# PCB_SATA_SFP.net
KiCad netlist of a schematic drawn in Altium Designer
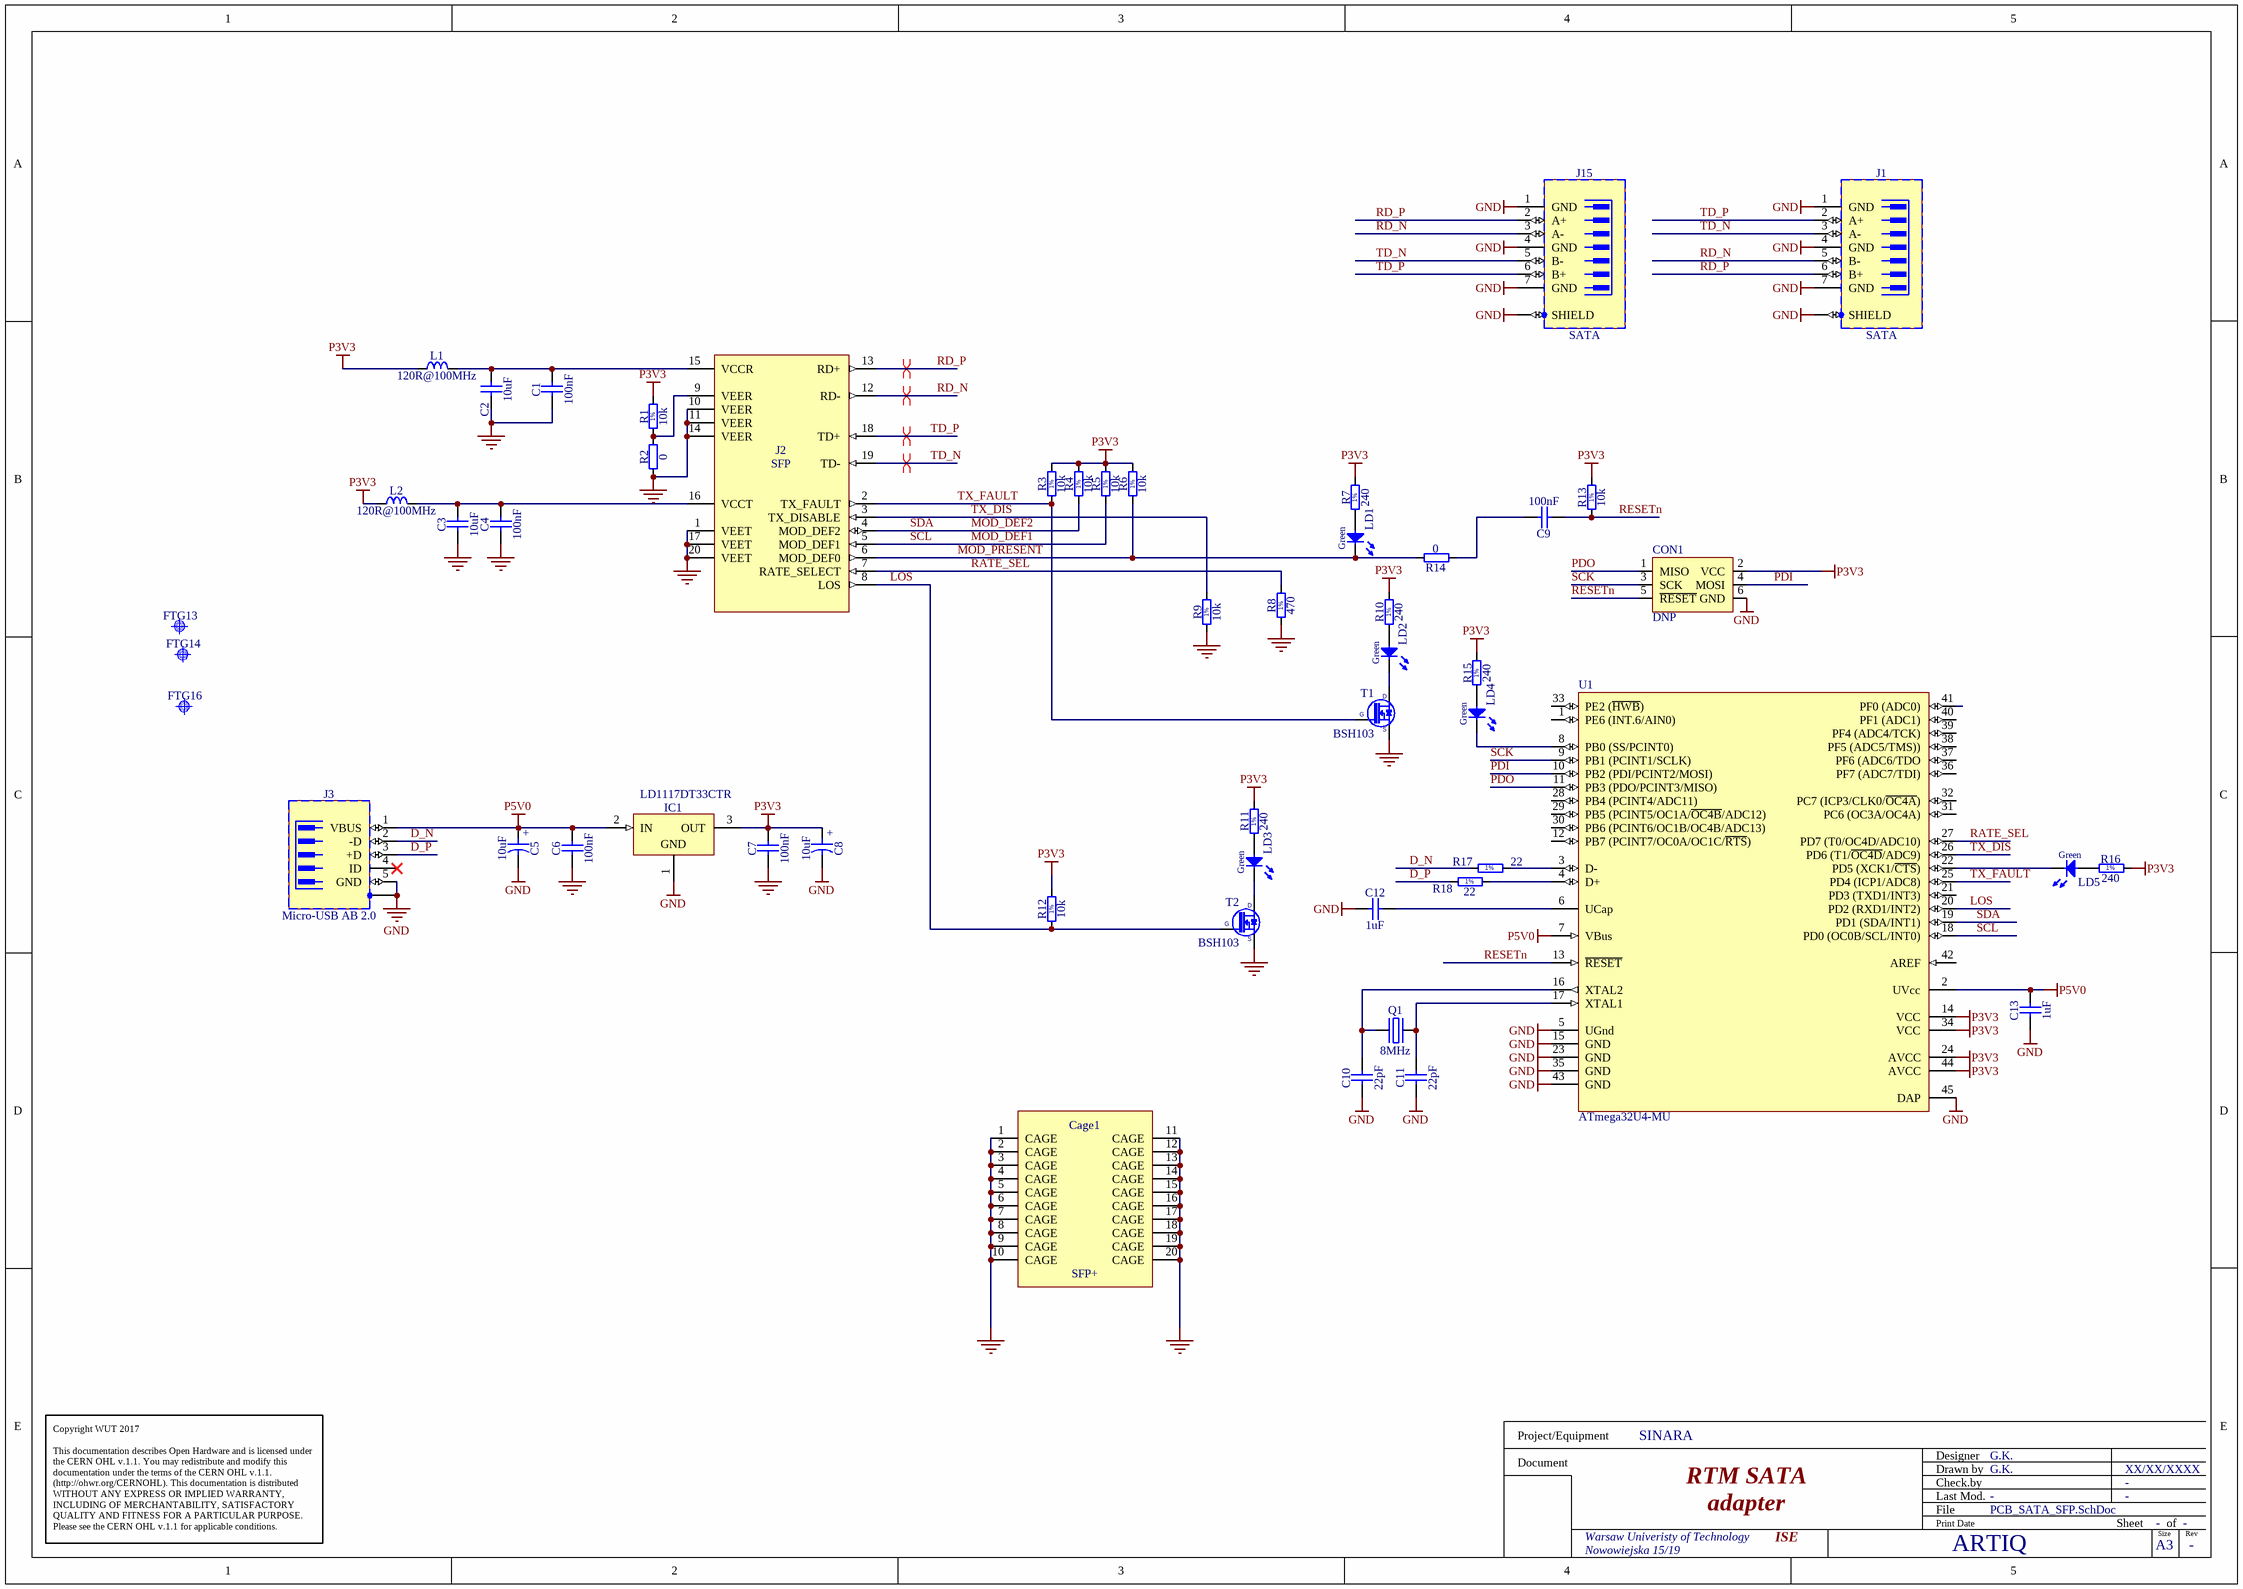
[diagram p0: PCB_SATA_SFP.SchDoc]

(export (version "E")
  (design (tool "Eeschema 10.0.6"))
  (components
    (comp (ref "C1")
      (value "100nF")
      (footprint "CAPC1608X87N")
      (description "Non-polarised capacitor")
      (fields
        (field (name "PART NUMBER") "CC0603_100NF_50V_10%_X5R")
        (field (name "VOLTAGE") "50V")
        (field (name "AUTHOR") "CERN DEM MR")
      )
      (libsource (lib "Capacitors") (part "Capacitor - non polarized"))
    )
    (comp (ref "C2")
      (value "10uF")
      (footprint "CAPC2012X95N")
      (description "Non-polarised capacitor")
      (fields
        (field (name "PART NUMBER") "CC0805_10UF_25V_10%_X5R")
        (field (name "VOLTAGE") "25V")
        (field (name "AUTHOR") "CERN DEM JLC")
      )
      (libsource (lib "Capacitors") (part "Capacitor - non polarized"))
    )
    (comp (ref "C3")
      (value "10uF")
      (footprint "CAPC2012X95N")
      (description "Non-polarised capacitor")
      (fields
        (field (name "PART NUMBER") "CC0805_10UF_25V_10%_X5R")
        (field (name "VOLTAGE") "25V")
        (field (name "AUTHOR") "CERN DEM JLC")
      )
      (libsource (lib "Capacitors") (part "Capacitor - non polarized"))
    )
    (comp (ref "C4")
      (value "100nF")
      (footprint "CAPC1608X87N")
      (description "Non-polarised capacitor")
      (fields
        (field (name "PART NUMBER") "CC0603_100NF_50V_10%_X5R")
        (field (name "VOLTAGE") "50V")
        (field (name "AUTHOR") "CERN DEM MR")
      )
      (libsource (lib "Capacitors") (part "Capacitor - non polarized"))
    )
    (comp (ref "C5")
      (value "10uF")
      (footprint "CAPMP6032X280N")
      (description "Polarised capacitor")
      (fields
        (field (name "PART NUMBER") "CTE6032-28_10UF_25V_10%_LESR0300")
        (field (name "VOLTAGE") "25V")
        (field (name "AUTHOR") "CERN DEM JLC")
      )
      (libsource (lib "Capacitors") (part "Capacitor - polarized"))
    )
    (comp (ref "C6")
      (value "100nF")
      (footprint "CAPC1608X87N")
      (description "Non-polarised capacitor")
      (fields
        (field (name "PART NUMBER") "CC0603_100NF_50V_10%_X5R")
        (field (name "VOLTAGE") "50V")
        (field (name "AUTHOR") "CERN DEM MR")
      )
      (libsource (lib "Capacitors") (part "Capacitor - non polarized"))
    )
    (comp (ref "C7")
      (value "100nF")
      (footprint "CAPC1608X87N")
      (description "Non-polarised capacitor")
      (fields
        (field (name "PART NUMBER") "CC0603_100NF_50V_10%_X5R")
        (field (name "VOLTAGE") "50V")
        (field (name "AUTHOR") "CERN DEM MR")
      )
      (libsource (lib "Capacitors") (part "Capacitor - non polarized"))
    )
    (comp (ref "C8")
      (value "10uF")
      (footprint "CAPMP6032X280N")
      (description "Polarised capacitor")
      (fields
        (field (name "PART NUMBER") "CTE6032-28_10UF_25V_10%_LESR0300")
        (field (name "VOLTAGE") "25V")
        (field (name "AUTHOR") "CERN DEM JLC")
      )
      (libsource (lib "Capacitors") (part "Capacitor - polarized"))
    )
    (comp (ref "C9")
      (value "100nF")
      (footprint "CAPC1608X87N")
      (description "Non-polarised capacitor")
      (fields
        (field (name "PART NUMBER") "CC0603_100NF_50V_10%_X5R")
        (field (name "VOLTAGE") "50V")
        (field (name "AUTHOR") "CERN DEM MR")
      )
      (libsource (lib "Capacitors") (part "Capacitor - non polarized"))
    )
    (comp (ref "C10")
      (value "22pF")
      (footprint "CAPC1608X87N")
      (description "Non-polarised capacitor")
      (fields
        (field (name "PART NUMBER") "CC0603_22PF_50V_5%_NP0")
        (field (name "VOLTAGE") "50V")
        (field (name "AUTHOR") "CERN DEM JLC")
      )
      (libsource (lib "Capacitors") (part "Capacitor - non polarized"))
    )
    (comp (ref "C11")
      (value "22pF")
      (footprint "CAPC1608X87N")
      (description "Non-polarised capacitor")
      (fields
        (field (name "PART NUMBER") "CC0603_22PF_50V_5%_NP0")
        (field (name "VOLTAGE") "50V")
        (field (name "AUTHOR") "CERN DEM JLC")
      )
      (libsource (lib "Capacitors") (part "Capacitor - non polarized"))
    )
    (comp (ref "C12")
      (value "1uF")
      (footprint "CAPC1608X87N")
      (description "Non-polarised capacitor")
      (fields
        (field (name "PART NUMBER") "CC0603_1UF_16V_10%_X7R")
        (field (name "VOLTAGE") "16V")
        (field (name "AUTHOR") "CERN DEM JLC")
      )
      (libsource (lib "Capacitors") (part "Capacitor - non polarized"))
    )
    (comp (ref "C13")
      (value "1uF")
      (footprint "CAPC1608X87N")
      (description "Non-polarised capacitor")
      (fields
        (field (name "PART NUMBER") "CC0603_1UF_16V_10%_X7R")
        (field (name "VOLTAGE") "16V")
        (field (name "AUTHOR") "CERN DEM JLC")
      )
      (libsource (lib "Capacitors") (part "Capacitor - non polarized"))
    )
    (comp (ref "Cage1")
      (value "SFP+")
      (footprint "TYCO_2007198-1")
      (description "SFP+ 1x1 Cage (20Pins)")
      (fields
        (field (name "PART NUMBER") "TYCO_2007198-1")
        (field (name "MANUFACTURER") "TYCO ELECTRONICS")
        (field (name "AUTHOR") "CERN DEM JLC")
      )
      (libsource (lib "Connectors") (part "SFP+ 1x1 Cage (20Pins)"))
    )
    (comp (ref "CON1")
      (value "DNP")
      (footprint "HEADER3x2")
      (description "6x 2.54mm SMT  dual row pin header")
      (libsource (lib "LIBRARY_SCH") (part "CON_ISP"))
    )
    (comp (ref "FTG13")
      (value "Use only in PCB")
      (footprint "FIDUCIAL_TOP_C100-200")
      (description "Fiducial Target")
      (fields (field (name "PART NUMBER") "FIDUCIAL_TARGET_C100-200") (field (name "AUTHOR") "CERN DEM JLC"))
      (libsource (lib "Eletro-mechanical") (part "Fiducial Target"))
    )
    (comp (ref "FTG14")
      (value "Use only in PCB")
      (footprint "FIDUCIAL_TOP_S100-200")
      (description "Fiducial Target")
      (fields (field (name "PART NUMBER") "FIDUCIAL_TARGET_S100-200") (field (name "AUTHOR") "CERN DEM JLC"))
      (libsource (lib "Eletro-mechanical") (part "Fiducial Target"))
    )
    (comp (ref "FTG16")
      (value "Use only in PCB")
      (footprint "FIDUCIAL_TOP_S100-200")
      (description "Fiducial Target")
      (fields (field (name "PART NUMBER") "FIDUCIAL_TARGET_S100-200") (field (name "AUTHOR") "CERN DEM JLC"))
      (libsource (lib "Eletro-mechanical") (part "Fiducial Target"))
    )
    (comp (ref "IC1")
      (value "LD1117DT33CTR")
      (footprint "TO228P972X240-3N-R540X510")
      (description "3-Terminal Regulator 1=GND 2=IN 3=OUT")
      (fields (field (name "MANUFACTURER") "ST MICROELECTRONICS") (field (name "AUTHOR") "CERN DEM JLC"))
      (libsource (lib "ICs And Semiconductors") (part "REG3 1GND-2IN-3OUT"))
    )
    (comp (ref "J1")
      (value "SATA")
      (footprint "3M_5607-4200-SH")
      (description "7 Pin + 1 Shield SATA Receptacle")
      (fields
        (field (name "PART NUMBER") "3M_5607-4200-SH")
        (field (name "MANUFACTURER") "3M")
        (field (name "AUTHOR") "CERN DEM JLC")
      )
      (libsource (lib "Connectors") (part "Connector SATA 7 Male + 1 Shield"))
    )
    (comp (ref "J2")
      (value "SFP")
      (footprint "TYCO_1367073-1")
      (description "20 Position SFP  Connector (Small Form-factor Pluggable)")
      (fields
        (field (name "PART NUMBER") "TYCO_1367073-1")
        (field (name "MANUFACTURER") "TYCO ELECTRONICS")
        (field (name "AUTHOR") "CERN DEM JLC")
      )
      (libsource (lib "Connectors") (part "SFPx1"))
    )
    (comp (ref "J3")
      (value "Micro-USB AB 2.0")
      (footprint "HIROSE_ZX62RD-AB-5P8")
      (description "5 Pin + 1 Shield USB Receptacle")
      (fields
        (field (name "PART NUMBER") "HIROSE_ZX62RD-AB-5P8")
        (field (name "MANUFACTURER") "HIROSE (HRS)")
        (field (name "AUTHOR") "CERN DEM JLC")
      )
      (libsource (lib "Connectors") (part "Connector USB 5 Pin + 1Shield"))
    )
    (comp (ref "J15")
      (value "SATA")
      (footprint "3M_5607-4200-SH")
      (description "7 Pin + 1 Shield SATA Receptacle")
      (fields
        (field (name "PART NUMBER") "3M_5607-4200-SH")
        (field (name "MANUFACTURER") "3M")
        (field (name "AUTHOR") "CERN DEM JLC")
      )
      (libsource (lib "Connectors") (part "Connector SATA 7 Male + 1 Shield"))
    )
    (comp (ref "L1")
      (value "120R@100MHz")
      (footprint "INDC1608X65N")
      (description "Inductor")
      (fields
        (field (name "PART NUMBER") "IND0603_MURATA_BLM18SG121TN1D")
        (field (name "POWER") "3A")
        (field (name "AUTHOR") "CERN DEM JLC")
      )
      (libsource (lib "Inductors & Transformers") (part "Inductor"))
    )
    (comp (ref "L2")
      (value "120R@100MHz")
      (footprint "INDC1608X65N")
      (description "Inductor")
      (fields
        (field (name "PART NUMBER") "IND0603_MURATA_BLM18SG121TN1D")
        (field (name "POWER") "3A")
        (field (name "AUTHOR") "CERN DEM JLC")
      )
      (libsource (lib "Inductors & Transformers") (part "Inductor"))
    )
    (comp (ref "LD1")
      (value "Green")
      (footprint "LED_KINGBRIGHT_KPH-1608CGCK")
      (description "LED Green 1C 2A")
      (fields
        (field (name "PART NUMBER") "LED_KINGBRIGHT_KPH-1608CGCK")
        (field (name "MANUFACTURER") "KINGBRIGHT")
        (field (name "AUTHOR") "CERN DEM JLC")
      )
      (libsource (lib "ICs And Semiconductors") (part "LED Green 1C 2A"))
    )
    (comp (ref "LD2")
      (value "Green")
      (footprint "LED_KINGBRIGHT_KPH-1608CGCK")
      (description "LED Green 1C 2A")
      (fields
        (field (name "PART NUMBER") "LED_KINGBRIGHT_KPH-1608CGCK")
        (field (name "MANUFACTURER") "KINGBRIGHT")
        (field (name "AUTHOR") "CERN DEM JLC")
      )
      (libsource (lib "ICs And Semiconductors") (part "LED Green 1C 2A"))
    )
    (comp (ref "LD3")
      (value "Green")
      (footprint "LED_KINGBRIGHT_KPH-1608CGCK")
      (description "LED Green 1C 2A")
      (fields
        (field (name "PART NUMBER") "LED_KINGBRIGHT_KPH-1608CGCK")
        (field (name "MANUFACTURER") "KINGBRIGHT")
        (field (name "AUTHOR") "CERN DEM JLC")
      )
      (libsource (lib "ICs And Semiconductors") (part "LED Green 1C 2A"))
    )
    (comp (ref "LD4")
      (value "Green")
      (footprint "LED_KINGBRIGHT_KPH-1608CGCK")
      (description "LED Green 1C 2A")
      (fields
        (field (name "PART NUMBER") "LED_KINGBRIGHT_KPH-1608CGCK")
        (field (name "MANUFACTURER") "KINGBRIGHT")
        (field (name "AUTHOR") "CERN DEM JLC")
      )
      (libsource (lib "ICs And Semiconductors") (part "LED Green 1C 2A"))
    )
    (comp (ref "LD5")
      (value "Green")
      (footprint "LED_KINGBRIGHT_KPH-1608CGCK")
      (description "LED Green 1C 2A")
      (fields
        (field (name "PART NUMBER") "LED_KINGBRIGHT_KPH-1608CGCK")
        (field (name "MANUFACTURER") "KINGBRIGHT")
        (field (name "AUTHOR") "CERN DEM JLC")
      )
      (libsource (lib "ICs And Semiconductors") (part "LED Green 1C 2A"))
    )
    (comp (ref "Q1")
      (value "8MHz")
      (footprint "XTAL_TXC_7A")
      (description "Quartz Crystal")
      (fields
        (field (name "PART NUMBER") "XTAL_8MHZ_TXC_7A-8.000MAAE-T")
        (field (name "MANUFACTURER") "TXC CORPORATION")
        (field (name "AUTHOR") "CERN DEM JLC")
      )
      (libsource (lib "ICs And Semiconductors") (part "Quartz Crystal"))
    )
    (comp (ref "R1")
      (value "10k")
      (footprint "RESC1608X55N")
      (description "Resistor - 1%")
      (fields
        (field (name "PART NUMBER") "R0603_10K_1%_0.1W_100PPM")
        (field (name "POWER") "0.1W")
        (field (name "AUTHOR") "CERN DEM JLC")
      )
      (libsource (lib "Resistors") (part "Resistor - 1%"))
    )
    (comp (ref "R2")
      (value "0")
      (footprint "RESC1608X55N")
      (description "Resistor")
      (fields
        (field (name "PART NUMBER") "R0603_0R_JUMPER")
        (field (name "MANUFACTURER") "GENERIC")
        (field (name "AUTHOR") "CERN DEM JLC")
      )
      (libsource (lib "Resistors") (part "Resistor"))
    )
    (comp (ref "R3")
      (value "10k")
      (footprint "RESC1608X55N")
      (description "Resistor - 1%")
      (fields
        (field (name "PART NUMBER") "R0603_10K_1%_0.1W_100PPM")
        (field (name "POWER") "0.1W")
        (field (name "AUTHOR") "CERN DEM JLC")
      )
      (libsource (lib "Resistors") (part "Resistor - 1%"))
    )
    (comp (ref "R4")
      (value "10k")
      (footprint "RESC1608X55N")
      (description "Resistor - 1%")
      (fields
        (field (name "PART NUMBER") "R0603_10K_1%_0.1W_100PPM")
        (field (name "POWER") "0.1W")
        (field (name "AUTHOR") "CERN DEM JLC")
      )
      (libsource (lib "Resistors") (part "Resistor - 1%"))
    )
    (comp (ref "R5")
      (value "10k")
      (footprint "RESC1608X55N")
      (description "Resistor - 1%")
      (fields
        (field (name "PART NUMBER") "R0603_10K_1%_0.1W_100PPM")
        (field (name "POWER") "0.1W")
        (field (name "AUTHOR") "CERN DEM JLC")
      )
      (libsource (lib "Resistors") (part "Resistor - 1%"))
    )
    (comp (ref "R6")
      (value "10k")
      (footprint "RESC1608X55N")
      (description "Resistor - 1%")
      (fields
        (field (name "PART NUMBER") "R0603_10K_1%_0.1W_100PPM")
        (field (name "POWER") "0.1W")
        (field (name "AUTHOR") "CERN DEM JLC")
      )
      (libsource (lib "Resistors") (part "Resistor - 1%"))
    )
    (comp (ref "R7")
      (value "240")
      (footprint "RESC1608X55N")
      (description "Resistor - 1%")
      (fields
        (field (name "PART NUMBER") "R0603_240R_1%_0.1W_100PPM")
        (field (name "POWER") "0.1W")
        (field (name "AUTHOR") "CERN DEM JLC")
      )
      (libsource (lib "Resistors") (part "Resistor - 1%"))
    )
    (comp (ref "R8")
      (value "470")
      (footprint "RESC1608X55N")
      (description "Resistor - 1%")
      (fields
        (field (name "PART NUMBER") "R0603_470R_1%_0.1W_100PPM")
        (field (name "POWER") "0.1W")
        (field (name "AUTHOR") "CERN DEM JLC")
      )
      (libsource (lib "Resistors") (part "Resistor - 1%"))
    )
    (comp (ref "R9")
      (value "10k")
      (footprint "RESC1608X55N")
      (description "Resistor - 1%")
      (fields
        (field (name "PART NUMBER") "R0603_10K_1%_0.1W_100PPM")
        (field (name "POWER") "0.1W")
        (field (name "AUTHOR") "CERN DEM JLC")
      )
      (libsource (lib "Resistors") (part "Resistor - 1%"))
    )
    (comp (ref "R10")
      (value "240")
      (footprint "RESC1608X55N")
      (description "Resistor - 1%")
      (fields
        (field (name "PART NUMBER") "R0603_240R_1%_0.1W_100PPM")
        (field (name "POWER") "0.1W")
        (field (name "AUTHOR") "CERN DEM JLC")
      )
      (libsource (lib "Resistors") (part "Resistor - 1%"))
    )
    (comp (ref "R11")
      (value "240")
      (footprint "RESC1608X55N")
      (description "Resistor - 1%")
      (fields
        (field (name "PART NUMBER") "R0603_240R_1%_0.1W_100PPM")
        (field (name "POWER") "0.1W")
        (field (name "AUTHOR") "CERN DEM JLC")
      )
      (libsource (lib "Resistors") (part "Resistor - 1%"))
    )
    (comp (ref "R12")
      (value "10k")
      (footprint "RESC1608X55N")
      (description "Resistor - 1%")
      (fields
        (field (name "PART NUMBER") "R0603_10K_1%_0.1W_100PPM")
        (field (name "POWER") "0.1W")
        (field (name "AUTHOR") "CERN DEM JLC")
      )
      (libsource (lib "Resistors") (part "Resistor - 1%"))
    )
    (comp (ref "R13")
      (value "10k")
      (footprint "RESC1608X55N")
      (description "Resistor - 1%")
      (fields
        (field (name "PART NUMBER") "R0603_10K_1%_0.1W_100PPM")
        (field (name "POWER") "0.1W")
        (field (name "AUTHOR") "CERN DEM JLC")
      )
      (libsource (lib "Resistors") (part "Resistor - 1%"))
    )
    (comp (ref "R14")
      (value "0")
      (footprint "RESC1608X55N")
      (description "Resistor")
      (fields
        (field (name "PART NUMBER") "R0603_0R_JUMPER")
        (field (name "MANUFACTURER") "GENERIC")
        (field (name "AUTHOR") "CERN DEM JLC")
      )
      (libsource (lib "Resistors") (part "Resistor"))
    )
    (comp (ref "R15")
      (value "240")
      (footprint "RESC1608X55N")
      (description "Resistor - 1%")
      (fields
        (field (name "PART NUMBER") "R0603_240R_1%_0.1W_100PPM")
        (field (name "POWER") "0.1W")
        (field (name "AUTHOR") "CERN DEM JLC")
      )
      (libsource (lib "Resistors") (part "Resistor - 1%"))
    )
    (comp (ref "R16")
      (value "240")
      (footprint "RESC1608X55N")
      (description "Resistor - 1%")
      (fields
        (field (name "PART NUMBER") "R0603_240R_1%_0.1W_100PPM")
        (field (name "POWER") "0.1W")
        (field (name "AUTHOR") "CERN DEM JLC")
      )
      (libsource (lib "Resistors") (part "Resistor - 1%"))
    )
    (comp (ref "R17")
      (value "22")
      (footprint "RESC1608X55N")
      (description "Resistor - 1%")
      (fields
        (field (name "PART NUMBER") "R0603_22R_1%_0.1W_100PPM")
        (field (name "POWER") "0.1W")
        (field (name "AUTHOR") "CERN DEM JLC")
      )
      (libsource (lib "Resistors") (part "Resistor - 1%"))
    )
    (comp (ref "R18")
      (value "22")
      (footprint "RESC1608X55N")
      (description "Resistor - 1%")
      (fields
        (field (name "PART NUMBER") "R0603_22R_1%_0.1W_100PPM")
        (field (name "POWER") "0.1W")
        (field (name "AUTHOR") "CERN DEM JLC")
      )
      (libsource (lib "Resistors") (part "Resistor - 1%"))
    )
    (comp (ref "T1")
      (value "BSH103")
      (footprint "SOT95P230X110-3N")
      (description "N-CHANNEL MOSFET WITH DIODE")
      (fields (field (name "MANUFACTURER") "NEXPERIA") (field (name "AUTHOR") "CERN DEM JLC"))
      (libsource (lib "ICs And Semiconductors") (part "N-MOSFET-D 1G 2S 3D"))
    )
    (comp (ref "T2")
      (value "BSH103")
      (footprint "SOT95P230X110-3N")
      (description "N-CHANNEL MOSFET WITH DIODE")
      (fields (field (name "MANUFACTURER") "NEXPERIA") (field (name "AUTHOR") "CERN DEM JLC"))
      (libsource (lib "ICs And Semiconductors") (part "N-MOSFET-D 1G 2S 3D"))
    )
    (comp (ref "U1")
      (value "ATmega32U4-MU")
      (footprint "44PW_N")
      (libsource (lib "Altium Content Vault") (part "MC-8B-ATM16U4-SQ45"))
    )
  )
  (nets
    (net (code "1") (name "/D_N") (class "Default")
      (node (ref "J3") (pin "2") (pinfunction "-D_2") (pintype "bidirectional"))
      (node (ref "R17") (pin "1") (pinfunction "1_1") (pintype "passive"))
    )
    (net (code "2") (name "/D_P") (class "Default")
      (node (ref "J3") (pin "3") (pinfunction "+D_3") (pintype "bidirectional"))
      (node (ref "R18") (pin "1") (pinfunction "1_1") (pintype "passive"))
    )
    (net (code "3") (name "/LOS") (class "Default")
      (node (ref "J2") (pin "8") (pinfunction "LOS_8") (pintype "output"))
      (node (ref "R12") (pin "1") (pinfunction "1_1") (pintype "passive"))
      (node (ref "T2") (pin "1") (pinfunction "G_1") (pintype "passive"))
      (node (ref "U1") (pin "20") (pinfunction "PD2_(RXD1/INT2)_20") (pintype "bidirectional"))
    )
    (net (code "4") (name "/MOD_DEF1") (class "Default")
      (node (ref "J2") (pin "5") (pinfunction "MOD_DEF1_5") (pintype "input"))
      (node (ref "R5") (pin "1") (pinfunction "1_1") (pintype "passive"))
      (node (ref "U1") (pin "18") (pinfunction "PD0_(OC0B/SCL/INT0)_18") (pintype "bidirectional"))
    )
    (net (code "5") (name "/MOD_DEF2") (class "Default")
      (node (ref "J2") (pin "4") (pinfunction "MOD_DEF2_4") (pintype "bidirectional"))
      (node (ref "R4") (pin "1") (pinfunction "1_1") (pintype "passive"))
      (node (ref "U1") (pin "19") (pinfunction "PD1_(SDA/INT1)_19") (pintype "bidirectional"))
    )
    (net (code "6") (name "/MOD_PRESENT") (class "Default")
      (node (ref "J2") (pin "6") (pinfunction "MOD_DEF0_6") (pintype "output"))
      (node (ref "LD1") (pin "1") (pinfunction "C_1") (pintype "passive"))
      (node (ref "R14") (pin "2") (pinfunction "2_2") (pintype "passive"))
      (node (ref "R6") (pin "1") (pinfunction "1_1") (pintype "passive"))
    )
    (net (code "7") (name "/PDI") (class "Default")
      (node (ref "CON1") (pin "4") (pinfunction "MOSI_4") (pintype "passive"))
      (node (ref "U1") (pin "10") (pinfunction "PB2_(PDI/PCINT2/MOSI)_10") (pintype "bidirectional"))
    )
    (net (code "8") (name "/PDO") (class "Default")
      (node (ref "CON1") (pin "1") (pinfunction "MISO_1") (pintype "passive"))
      (node (ref "U1") (pin "11") (pinfunction "PB3_(PDO/PCINT3/MISO)_11") (pintype "bidirectional"))
    )
    (net (code "9") (name "/RATE_SEL") (class "Default")
      (node (ref "J2") (pin "7") (pinfunction "RATE_SELECT_7") (pintype "input"))
      (node (ref "R8") (pin "2") (pinfunction "2_2") (pintype "passive"))
      (node (ref "U1") (pin "27") (pinfunction "PD7_(T0/OC4D/ADC10)_27") (pintype "bidirectional"))
    )
    (net (code "10") (name "/RD_N") (class "Default")
      (node (ref "J1") (pin "5") (pinfunction "B-_5") (pintype "bidirectional"))
      (node (ref "J15") (pin "3") (pinfunction "A-_3") (pintype "bidirectional"))
      (node (ref "J2") (pin "12") (pinfunction "RD-_12") (pintype "output"))
    )
    (net (code "11") (name "/RD_P") (class "Default")
      (node (ref "J1") (pin "6") (pinfunction "B+_6") (pintype "bidirectional"))
      (node (ref "J15") (pin "2") (pinfunction "A+_2") (pintype "bidirectional"))
      (node (ref "J2") (pin "13") (pinfunction "RD+_13") (pintype "output"))
    )
    (net (code "12") (name "/RESETn") (class "Default")
      (node (ref "C9") (pin "1") (pinfunction "1_1") (pintype "passive"))
      (node (ref "CON1") (pin "5") (pinfunction "~{RESET}_5") (pintype "passive"))
      (node (ref "R13") (pin "1") (pinfunction "1_1") (pintype "passive"))
      (node (ref "U1") (pin "13") (pinfunction "~{RESET}_13") (pintype "input"))
    )
    (net (code "13") (name "/SCK") (class "Default")
      (node (ref "CON1") (pin "3") (pinfunction "SCK_3") (pintype "passive"))
      (node (ref "U1") (pin "9") (pinfunction "PB1_(PCINT1/SCLK)_9") (pintype "bidirectional"))
    )
    (net (code "14") (name "/TD_N") (class "Default")
      (node (ref "J1") (pin "3") (pinfunction "A-_3") (pintype "bidirectional"))
      (node (ref "J15") (pin "5") (pinfunction "B-_5") (pintype "bidirectional"))
      (node (ref "J2") (pin "19") (pinfunction "TD-_19") (pintype "input"))
    )
    (net (code "15") (name "/TD_P") (class "Default")
      (node (ref "J1") (pin "2") (pinfunction "A+_2") (pintype "bidirectional"))
      (node (ref "J15") (pin "6") (pinfunction "B+_6") (pintype "bidirectional"))
      (node (ref "J2") (pin "18") (pinfunction "TD+_18") (pintype "input"))
    )
    (net (code "16") (name "/TX_DIS") (class "Default")
      (node (ref "J2") (pin "3") (pinfunction "TX_DISABLE_3") (pintype "input"))
      (node (ref "R9") (pin "2") (pinfunction "2_2") (pintype "passive"))
      (node (ref "U1") (pin "26") (pinfunction "PD6_(T1/~{OC4D}/ADC9)_26") (pintype "bidirectional"))
    )
    (net (code "17") (name "/TX_FAULT") (class "Default")
      (node (ref "J2") (pin "2") (pinfunction "TX_FAULT_2") (pintype "output"))
      (node (ref "R3") (pin "1") (pinfunction "1_1") (pintype "passive"))
      (node (ref "T1") (pin "1") (pinfunction "G_1") (pintype "passive"))
      (node (ref "U1") (pin "25") (pinfunction "PD4_(ICP1/ADC8)_25") (pintype "bidirectional"))
    )
    (net (code "18") (name "GND") (class "Default")
      (node (ref "C1") (pin "1") (pinfunction "1_1") (pintype "passive"))
      (node (ref "C10") (pin "1") (pinfunction "1_1") (pintype "passive"))
      (node (ref "C11") (pin "1") (pinfunction "1_1") (pintype "passive"))
      (node (ref "C12") (pin "1") (pinfunction "1_1") (pintype "passive"))
      (node (ref "C13") (pin "1") (pinfunction "1_1") (pintype "passive"))
      (node (ref "C2") (pin "1") (pinfunction "1_1") (pintype "passive"))
      (node (ref "C3") (pin "1") (pinfunction "1_1") (pintype "passive"))
      (node (ref "C4") (pin "1") (pinfunction "1_1") (pintype "passive"))
      (node (ref "C5") (pin "2") (pinfunction "2_2") (pintype "passive"))
      (node (ref "C6") (pin "1") (pinfunction "1_1") (pintype "passive"))
      (node (ref "C7") (pin "1") (pinfunction "1_1") (pintype "passive"))
      (node (ref "C8") (pin "2") (pinfunction "2_2") (pintype "passive"))
      (node (ref "CON1") (pin "6") (pinfunction "GND_6") (pintype "passive"))
      (node (ref "Cage1") (pin "1") (pinfunction "CAGE_1") (pintype "power_in"))
      (node (ref "Cage1") (pin "10") (pinfunction "CAGE_10") (pintype "power_in"))
      (node (ref "Cage1") (pin "11") (pinfunction "CAGE_11") (pintype "power_in"))
      (node (ref "Cage1") (pin "12") (pinfunction "CAGE_12") (pintype "power_in"))
      (node (ref "Cage1") (pin "13") (pinfunction "CAGE_13") (pintype "power_in"))
      (node (ref "Cage1") (pin "14") (pinfunction "CAGE_14") (pintype "power_in"))
      (node (ref "Cage1") (pin "15") (pinfunction "CAGE_15") (pintype "power_in"))
      (node (ref "Cage1") (pin "16") (pinfunction "CAGE_16") (pintype "power_in"))
      (node (ref "Cage1") (pin "17") (pinfunction "CAGE_17") (pintype "power_in"))
      (node (ref "Cage1") (pin "18") (pinfunction "CAGE_18") (pintype "power_in"))
      (node (ref "Cage1") (pin "19") (pinfunction "CAGE_19") (pintype "power_in"))
      (node (ref "Cage1") (pin "2") (pinfunction "CAGE_2") (pintype "power_in"))
      (node (ref "Cage1") (pin "20") (pinfunction "CAGE_20") (pintype "power_in"))
      (node (ref "Cage1") (pin "3") (pinfunction "CAGE_3") (pintype "power_in"))
      (node (ref "Cage1") (pin "4") (pinfunction "CAGE_4") (pintype "power_in"))
      (node (ref "Cage1") (pin "5") (pinfunction "CAGE_5") (pintype "power_in"))
      (node (ref "Cage1") (pin "6") (pinfunction "CAGE_6") (pintype "power_in"))
      (node (ref "Cage1") (pin "7") (pinfunction "CAGE_7") (pintype "power_in"))
      (node (ref "Cage1") (pin "8") (pinfunction "CAGE_8") (pintype "power_in"))
      (node (ref "Cage1") (pin "9") (pinfunction "CAGE_9") (pintype "power_in"))
      (node (ref "IC1") (pin "1") (pinfunction "GND_1") (pintype "power_in"))
      (node (ref "J1") (pin "1") (pinfunction "GND_1") (pintype "power_in"))
      (node (ref "J1") (pin "4") (pinfunction "GND_4") (pintype "power_in"))
      (node (ref "J1") (pin "7") (pinfunction "GND_7") (pintype "power_in"))
      (node (ref "J1") (pin "8") (pinfunction "SHIELD_8") (pintype "bidirectional"))
      (node (ref "J15") (pin "1") (pinfunction "GND_1") (pintype "power_in"))
      (node (ref "J15") (pin "4") (pinfunction "GND_4") (pintype "power_in"))
      (node (ref "J15") (pin "7") (pinfunction "GND_7") (pintype "power_in"))
      (node (ref "J15") (pin "8") (pinfunction "SHIELD_8") (pintype "bidirectional"))
      (node (ref "J2") (pin "1") (pinfunction "VEET_1") (pintype "power_in"))
      (node (ref "J2") (pin "10") (pinfunction "VEER_10") (pintype "power_in"))
      (node (ref "J2") (pin "11") (pinfunction "VEER_11") (pintype "power_in"))
      (node (ref "J2") (pin "14") (pinfunction "VEER_14") (pintype "power_in"))
      (node (ref "J2") (pin "17") (pinfunction "VEET_17") (pintype "power_in"))
      (node (ref "J2") (pin "20") (pinfunction "VEET_20") (pintype "power_in"))
      (node (ref "J3") (pin "5") (pinfunction "GND_5") (pintype "bidirectional"))
      (node (ref "J3") (pin "6") (pinfunction "SH_6") (pintype "power_in"))
      (node (ref "R2") (pin "1") (pinfunction "1_1") (pintype "passive"))
      (node (ref "R8") (pin "1") (pinfunction "1_1") (pintype "passive"))
      (node (ref "R9") (pin "1") (pinfunction "1_1") (pintype "passive"))
      (node (ref "T1") (pin "2") (pinfunction "S_2") (pintype "passive"))
      (node (ref "T2") (pin "2") (pinfunction "S_2") (pintype "passive"))
      (node (ref "U1") (pin "15") (pinfunction "GND_15") (pintype "power_in"))
      (node (ref "U1") (pin "23") (pinfunction "GND_23") (pintype "power_in"))
      (node (ref "U1") (pin "35") (pinfunction "GND_35") (pintype "power_in"))
      (node (ref "U1") (pin "43") (pinfunction "GND_43") (pintype "power_in"))
      (node (ref "U1") (pin "45") (pinfunction "DAP_45") (pintype "power_in"))
      (node (ref "U1") (pin "5") (pinfunction "UGnd_5") (pintype "power_in"))
    )
    (net (code "19") (name "Net-(C9-Pad2)") (class "Default")
      (node (ref "C9") (pin "2") (pinfunction "2_2") (pintype "passive"))
      (node (ref "R14") (pin "1") (pinfunction "1_1") (pintype "passive"))
    )
    (net (code "20") (name "Net-(J2-VCCR)") (class "Default")
      (node (ref "C1") (pin "2") (pinfunction "2_2") (pintype "passive"))
      (node (ref "C2") (pin "2") (pinfunction "2_2") (pintype "passive"))
      (node (ref "J2") (pin "15") (pinfunction "VCCR_15") (pintype "power_in"))
      (node (ref "L1") (pin "2") (pinfunction "2_2") (pintype "passive"))
    )
    (net (code "21") (name "Net-(J2-VCCT)") (class "Default")
      (node (ref "C3") (pin "2") (pinfunction "2_2") (pintype "passive"))
      (node (ref "C4") (pin "2") (pinfunction "2_2") (pintype "passive"))
      (node (ref "J2") (pin "16") (pinfunction "VCCT_16") (pintype "power_in"))
      (node (ref "L2") (pin "2") (pinfunction "2_2") (pintype "passive"))
    )
    (net (code "22") (name "Net-(J2-VEER-Pad9)") (class "Default")
      (node (ref "J2") (pin "9") (pinfunction "VEER_9") (pintype "power_in"))
      (node (ref "R1") (pin "1") (pinfunction "1_1") (pintype "passive"))
      (node (ref "R2") (pin "2") (pinfunction "2_2") (pintype "passive"))
    )
    (net (code "23") (name "Net-(LD1-A)") (class "Default")
      (node (ref "LD1") (pin "2") (pinfunction "A_2") (pintype "passive"))
      (node (ref "R7") (pin "1") (pinfunction "1_1") (pintype "passive"))
    )
    (net (code "24") (name "Net-(LD2-A)") (class "Default")
      (node (ref "LD2") (pin "2") (pinfunction "A_2") (pintype "passive"))
      (node (ref "R10") (pin "1") (pinfunction "1_1") (pintype "passive"))
    )
    (net (code "25") (name "Net-(LD2-C)") (class "Default")
      (node (ref "LD2") (pin "1") (pinfunction "C_1") (pintype "passive"))
      (node (ref "T1") (pin "3") (pinfunction "D_3") (pintype "passive"))
    )
    (net (code "26") (name "Net-(LD3-A)") (class "Default")
      (node (ref "LD3") (pin "2") (pinfunction "A_2") (pintype "passive"))
      (node (ref "R11") (pin "1") (pinfunction "1_1") (pintype "passive"))
    )
    (net (code "27") (name "Net-(LD3-C)") (class "Default")
      (node (ref "LD3") (pin "1") (pinfunction "C_1") (pintype "passive"))
      (node (ref "T2") (pin "3") (pinfunction "D_3") (pintype "passive"))
    )
    (net (code "28") (name "Net-(LD4-A)") (class "Default")
      (node (ref "LD4") (pin "2") (pinfunction "A_2") (pintype "passive"))
      (node (ref "R15") (pin "1") (pinfunction "1_1") (pintype "passive"))
    )
    (net (code "29") (name "Net-(LD4-C)") (class "Default")
      (node (ref "LD4") (pin "1") (pinfunction "C_1") (pintype "passive"))
      (node (ref "U1") (pin "8") (pinfunction "PB0_(SS/PCINT0)_8") (pintype "bidirectional"))
    )
    (net (code "30") (name "Net-(LD5-A)") (class "Default")
      (node (ref "LD5") (pin "2") (pinfunction "A_2") (pintype "passive"))
      (node (ref "R16") (pin "1") (pinfunction "1_1") (pintype "passive"))
    )
    (net (code "31") (name "Net-(LD5-C)") (class "Default")
      (node (ref "LD5") (pin "1") (pinfunction "C_1") (pintype "passive"))
      (node (ref "U1") (pin "22") (pinfunction "PD5_(XCK1/~{CTS})_22") (pintype "bidirectional"))
    )
    (net (code "32") (name "Net-(Q1-OSC1)") (class "Default")
      (node (ref "C10") (pin "2") (pinfunction "2_2") (pintype "passive"))
      (node (ref "Q1") (pin "1") (pinfunction "OSC1_1") (pintype "passive"))
      (node (ref "U1") (pin "16") (pinfunction "XTAL2_16") (pintype "output"))
    )
    (net (code "33") (name "Net-(Q1-OSC2)") (class "Default")
      (node (ref "C11") (pin "2") (pinfunction "2_2") (pintype "passive"))
      (node (ref "Q1") (pin "2") (pinfunction "OSC2_2") (pintype "passive"))
      (node (ref "U1") (pin "17") (pinfunction "XTAL1_17") (pintype "input"))
    )
    (net (code "34") (name "Net-(U1-D+)") (class "Default")
      (node (ref "R18") (pin "2") (pinfunction "2_2") (pintype "passive"))
      (node (ref "U1") (pin "4") (pinfunction "D+_4") (pintype "bidirectional"))
    )
    (net (code "35") (name "Net-(U1-D-)") (class "Default")
      (node (ref "R17") (pin "2") (pinfunction "2_2") (pintype "passive"))
      (node (ref "U1") (pin "3") (pinfunction "D-_3") (pintype "bidirectional"))
    )
    (net (code "36") (name "Net-(U1-UCap)") (class "Default")
      (node (ref "C12") (pin "2") (pinfunction "2_2") (pintype "passive"))
      (node (ref "U1") (pin "6") (pinfunction "UCap_6") (pintype "passive"))
    )
    (net (code "37") (name "P3V3") (class "Default")
      (node (ref "C7") (pin "2") (pinfunction "2_2") (pintype "passive"))
      (node (ref "C8") (pin "1") (pinfunction "1_1") (pintype "passive"))
      (node (ref "CON1") (pin "2") (pinfunction "VCC_2") (pintype "passive"))
      (node (ref "IC1") (pin "3") (pinfunction "OUT_3") (pintype "power_in"))
      (node (ref "L1") (pin "1") (pinfunction "1_1") (pintype "passive"))
      (node (ref "L2") (pin "1") (pinfunction "1_1") (pintype "passive"))
      (node (ref "R1") (pin "2") (pinfunction "2_2") (pintype "passive"))
      (node (ref "R10") (pin "2") (pinfunction "2_2") (pintype "passive"))
      (node (ref "R11") (pin "2") (pinfunction "2_2") (pintype "passive"))
      (node (ref "R12") (pin "2") (pinfunction "2_2") (pintype "passive"))
      (node (ref "R13") (pin "2") (pinfunction "2_2") (pintype "passive"))
      (node (ref "R15") (pin "2") (pinfunction "2_2") (pintype "passive"))
      (node (ref "R16") (pin "2") (pinfunction "2_2") (pintype "passive"))
      (node (ref "R3") (pin "2") (pinfunction "2_2") (pintype "passive"))
      (node (ref "R4") (pin "2") (pinfunction "2_2") (pintype "passive"))
      (node (ref "R5") (pin "2") (pinfunction "2_2") (pintype "passive"))
      (node (ref "R6") (pin "2") (pinfunction "2_2") (pintype "passive"))
      (node (ref "R7") (pin "2") (pinfunction "2_2") (pintype "passive"))
      (node (ref "U1") (pin "14") (pinfunction "VCC_14") (pintype "power_in"))
      (node (ref "U1") (pin "24") (pinfunction "AVCC_24") (pintype "power_in"))
      (node (ref "U1") (pin "34") (pinfunction "VCC_34") (pintype "power_in"))
      (node (ref "U1") (pin "44") (pinfunction "AVCC_44") (pintype "power_in"))
    )
    (net (code "38") (name "P5V0") (class "Default")
      (node (ref "C13") (pin "2") (pinfunction "2_2") (pintype "passive"))
      (node (ref "C5") (pin "1") (pinfunction "1_1") (pintype "passive"))
      (node (ref "C6") (pin "2") (pinfunction "2_2") (pintype "passive"))
      (node (ref "IC1") (pin "2") (pinfunction "IN_2") (pintype "input"))
      (node (ref "J3") (pin "1") (pinfunction "VBUS_1") (pintype "bidirectional"))
      (node (ref "U1") (pin "2") (pinfunction "UVcc_2") (pintype "power_in"))
      (node (ref "U1") (pin "7") (pinfunction "VBus_7") (pintype "input"))
    )
    (net (code "39") (name "unconnected-(J3-ID-Pad4)") (class "Default")
      (node (ref "J3") (pin "4") (pinfunction "ID_4") (pintype "passive+no_connect"))
    )
    (net (code "40") (name "unconnected-(U1-AREF-Pad42)") (class "Default")
      (node (ref "U1") (pin "42") (pinfunction "AREF_42") (pintype "input"))
    )
    (net (code "41") (name "unconnected-(U1-PB4_(PCINT4{slash}ADC11)-Pad28)") (class "Default")
      (node (ref "U1") (pin "28") (pinfunction "PB4_(PCINT4/ADC11)_28") (pintype "bidirectional"))
    )
    (net (code "42") (name "unconnected-(U1-PB5_(PCINT5{slash}OC1A{slash}~{OC4B}{slash}ADC12)-Pad29)") (class "Default")
      (node (ref "U1") (pin "29") (pinfunction "PB5_(PCINT5/OC1A/~{OC4B}/ADC12)_29") (pintype "bidirectional"))
    )
    (net (code "43") (name "unconnected-(U1-PB6_(PCINT6{slash}OC1B{slash}OC4B{slash}ADC13)-Pad30)") (class "Default")
      (node (ref "U1") (pin "30") (pinfunction "PB6_(PCINT6/OC1B/OC4B/ADC13)_30") (pintype "bidirectional"))
    )
    (net (code "44") (name "unconnected-(U1-PB7_(PCINT7{slash}OC0A{slash}OC1C{slash}~{RTS})-Pad12)") (class "Default")
      (node (ref "U1") (pin "12") (pinfunction "PB7_(PCINT7/OC0A/OC1C/~{RTS})_12") (pintype "bidirectional"))
    )
    (net (code "45") (name "unconnected-(U1-PC6_(OC3A{slash}OC4A)-Pad31)") (class "Default")
      (node (ref "U1") (pin "31") (pinfunction "PC6_(OC3A/OC4A)_31") (pintype "bidirectional"))
    )
    (net (code "46") (name "unconnected-(U1-PC7_(ICP3{slash}CLK0{slash}~{OC4A})-Pad32)") (class "Default")
      (node (ref "U1") (pin "32") (pinfunction "PC7_(ICP3/CLK0/~{OC4A})_32") (pintype "bidirectional"))
    )
    (net (code "47") (name "unconnected-(U1-PD3_(TXD1{slash}INT3)-Pad21)") (class "Default")
      (node (ref "U1") (pin "21") (pinfunction "PD3_(TXD1/INT3)_21") (pintype "bidirectional"))
    )
    (net (code "48") (name "unconnected-(U1-PE2_(~{HWB})-Pad33)") (class "Default")
      (node (ref "U1") (pin "33") (pinfunction "PE2_(~{HWB})_33") (pintype "bidirectional"))
    )
    (net (code "49") (name "unconnected-(U1-PE6_(INT.6{slash}AIN0)-Pad1)") (class "Default")
      (node (ref "U1") (pin "1") (pinfunction "PE6_(INT.6/AIN0)_1") (pintype "bidirectional"))
    )
    (net (code "50") (name "unconnected-(U1-PF0_(ADC0)-Pad41)") (class "Default")
      (node (ref "U1") (pin "41") (pinfunction "PF0_(ADC0)_41") (pintype "bidirectional"))
    )
    (net (code "51") (name "unconnected-(U1-PF1_(ADC1)-Pad40)") (class "Default")
      (node (ref "U1") (pin "40") (pinfunction "PF1_(ADC1)_40") (pintype "bidirectional"))
    )
    (net (code "52") (name "unconnected-(U1-PF4_(ADC4{slash}TCK)-Pad39)") (class "Default")
      (node (ref "U1") (pin "39") (pinfunction "PF4_(ADC4/TCK)_39") (pintype "bidirectional"))
    )
    (net (code "53") (name "unconnected-(U1-PF5_(ADC5{slash}TMS))-Pad38)") (class "Default")
      (node (ref "U1") (pin "38") (pinfunction "PF5_(ADC5/TMS))_38") (pintype "bidirectional"))
    )
    (net (code "54") (name "unconnected-(U1-PF6_(ADC6{slash}TDO-Pad37)") (class "Default")
      (node (ref "U1") (pin "37") (pinfunction "PF6_(ADC6/TDO_37") (pintype "bidirectional"))
    )
    (net (code "55") (name "unconnected-(U1-PF7_(ADC7{slash}TDI)-Pad36)") (class "Default")
      (node (ref "U1") (pin "36") (pinfunction "PF7_(ADC7/TDI)_36") (pintype "bidirectional"))
    )
  )
)
